# PuppyLight.net
KiCad netlist of a schematic drawn in Altium Designer
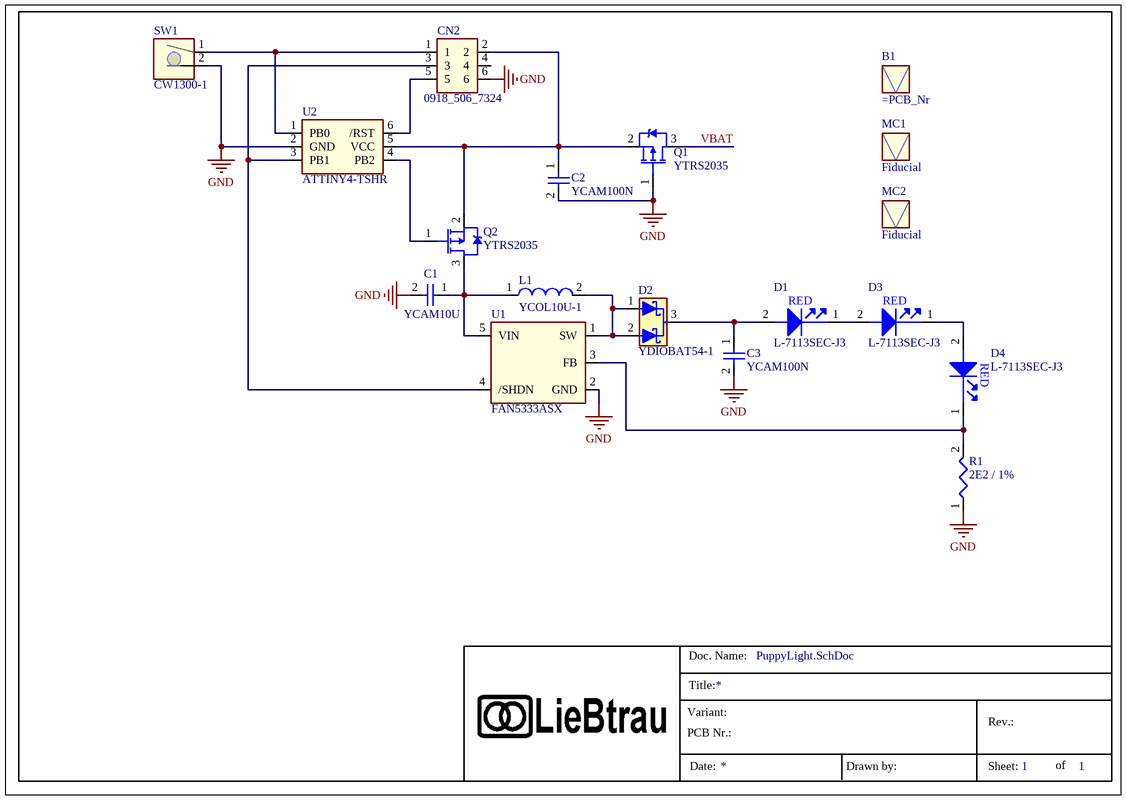
[diagram p0: PuppyLight.SchDoc]

(export (version "E")
  (design (tool "Eeschema 10.0.6"))
  (components
    (comp (ref "B1")
      (value "~")
      (footprint "MC_BoardNr")
      (fields (field (name "PART NUMBER") "BARE_PCB"))
      (libsource (lib "Testing") (part "BD_PCB"))
    )
    (comp (ref "C1") (value "YCAM10U") (footprint "CA_1206") (libsource (lib "Testing") (part "CA_NONPOL")))
    (comp (ref "C2") (value "YCAM100N") (footprint "CA_1206") (libsource (lib "Testing") (part "CA_NONPOL")))
    (comp (ref "C3") (value "YCAM100N") (footprint "CA_1206") (libsource (lib "Testing") (part "CA_NONPOL")))
    (comp (ref "CN2")
      (value "0918_506_7324")
      (footprint "CN_HARTING_918506X324")
      (fields (field (name "MANUFACTURER") "Harting"))
      (libsource (lib "Testing") (part "CN_2x3P"))
    )
    (comp (ref "D1")
      (value "L-7113SEC-J3")
      (footprint "DI_LED_5MM")
      (fields (field (name "MANUFACTURER") "Kingbright"))
      (libsource (lib "Testing") (part "DI_LED_RED_2"))
    )
    (comp (ref "D2")
      (value "YDIOBAT54-1")
      (footprint "SC_SOT23")
      (description "Dual Schottky Barrier Diode Common Cathode")
      (fields (field (name "MANUFACTURER") "Fairchild Semiconductor"))
      (libsource (lib "Testing") (part "DI_SCHOTTKY_2_CC"))
    )
    (comp (ref "D3")
      (value "L-7113SEC-J3")
      (footprint "DI_LED_5MM")
      (fields (field (name "MANUFACTURER") "Kingbright"))
      (libsource (lib "Testing") (part "DI_LED_RED_2"))
    )
    (comp (ref "D4")
      (value "L-7113SEC-J3")
      (footprint "DI_LED_5MM")
      (fields (field (name "MANUFACTURER") "Kingbright"))
      (libsource (lib "Testing") (part "DI_LED_RED_2"))
    )
    (comp (ref "L1")
      (value "YCOL10U-1")
      (footprint "CL_VISHAY_IHLP-2525CZ-01")
      (fields (field (name "MANUFACTURER") "Vishay Dale"))
      (libsource (lib "Testing") (part "CL_COIL"))
    )
    (comp (ref "MC1")
      (value "Fiducial")
      (footprint "MC_FIDUCIAL")
      (libsource (lib "Testing") (part "MC_MechPart_No_BOM"))
    )
    (comp (ref "MC2")
      (value "Fiducial")
      (footprint "MC_FIDUCIAL")
      (libsource (lib "Testing") (part "MC_MechPart_No_BOM"))
    )
    (comp (ref "Q1")
      (value "YTRS2035")
      (footprint "SC_SOT23")
      (fields (field (name "MANUFACTURER") "Diodes Inc."))
      (libsource (lib "Testing") (part "TR_PMOS"))
    )
    (comp (ref "Q2")
      (value "YTRS2035")
      (footprint "SC_SOT23")
      (fields (field (name "MANUFACTURER") "Diodes Inc."))
      (libsource (lib "Testing") (part "TR_PMOS"))
    )
    (comp (ref "R1")
      (value "2E2 / 1%")
      (footprint "RE_1206")
      (description "Resistor")
      (fields (field (name "PART NUMBER") "ASC1206-2R2FT5") (field (name "MANUFACTURER") "Welwyn"))
      (libsource (lib "Testing") (part "RE_RES"))
    )
    (comp (ref "SW1")
      (value "CW1300-1")
      (footprint "SW_TILT_Comus_CW1300-1")
      (fields (field (name "MANUFACTURER") "Comus"))
      (libsource (lib "Testing") (part "SW_TILT"))
    )
    (comp (ref "U1")
      (value "FAN5333ASX")
      (footprint "SC_SOT23-5AM")
      (fields (field (name "MANUFACTURER") "Fairchild Semi"))
      (libsource (lib "Testing") (part "IC_FAN5333"))
    )
    (comp (ref "U2")
      (value "ATTINY4-TSHR")
      (footprint "SC_SOT23-6")
      (fields (field (name "MANUFACTURER") "Atmel"))
      (libsource (lib "Testing") (part "IC_ATMEL_ATTINY9"))
    )
  )
  (nets
    (net (code "1") (name "/VBAT") (class "Default")
      (node (ref "Q1") (pin "3") (pinfunction "D_3") (pintype "passive"))
    )
    (net (code "2") (name "GND") (class "Default")
      (node (ref "C1") (pin "2") (pinfunction "2_2") (pintype "passive"))
      (node (ref "C2") (pin "2") (pinfunction "2_2") (pintype "passive"))
      (node (ref "C3") (pin "2") (pinfunction "2_2") (pintype "passive"))
      (node (ref "CN2") (pin "6") (pinfunction "6_6") (pintype "passive"))
      (node (ref "Q1") (pin "1") (pinfunction "G_1") (pintype "passive"))
      (node (ref "R1") (pin "1") (pinfunction "1_1") (pintype "passive"))
      (node (ref "SW1") (pin "2") (pinfunction "2_2") (pintype "passive"))
      (node (ref "U1") (pin "2") (pinfunction "GND_2") (pintype "passive"))
      (node (ref "U2") (pin "2") (pinfunction "GND_2") (pintype "passive"))
    )
    (net (code "3") (name "Net-(D1-A)") (class "Default")
      (node (ref "D1") (pin "1") (pinfunction "A_1") (pintype "passive"))
      (node (ref "D3") (pin "2") (pinfunction "C_2") (pintype "passive"))
    )
    (net (code "4") (name "Net-(D1-C)") (class "Default")
      (node (ref "C3") (pin "1") (pinfunction "1_1") (pintype "passive"))
      (node (ref "D1") (pin "2") (pinfunction "C_2") (pintype "passive"))
      (node (ref "D2") (pin "3") (pinfunction "C_3") (pintype "passive"))
    )
    (net (code "5") (name "Net-(D2-A1)") (class "Default")
      (node (ref "D2") (pin "1") (pinfunction "A1_1") (pintype "passive"))
      (node (ref "D2") (pin "2") (pinfunction "A2_2") (pintype "passive"))
      (node (ref "L1") (pin "2") (pinfunction "2_2") (pintype "passive"))
      (node (ref "U1") (pin "1") (pinfunction "SW_1") (pintype "passive"))
    )
    (net (code "6") (name "Net-(D3-A)") (class "Default")
      (node (ref "D3") (pin "1") (pinfunction "A_1") (pintype "passive"))
      (node (ref "D4") (pin "2") (pinfunction "C_2") (pintype "passive"))
    )
    (net (code "7") (name "Net-(D4-A)") (class "Default")
      (node (ref "D4") (pin "1") (pinfunction "A_1") (pintype "passive"))
      (node (ref "R1") (pin "2") (pinfunction "2_2") (pintype "passive"))
      (node (ref "U1") (pin "3") (pinfunction "FB_3") (pintype "passive"))
    )
    (net (code "8") (name "Net-(Q1-S)") (class "Default")
      (node (ref "C2") (pin "1") (pinfunction "1_1") (pintype "passive"))
      (node (ref "CN2") (pin "2") (pinfunction "2_2") (pintype "passive"))
      (node (ref "Q1") (pin "2") (pinfunction "S_2") (pintype "passive"))
      (node (ref "Q2") (pin "2") (pinfunction "S_2") (pintype "passive"))
      (node (ref "U2") (pin "5") (pinfunction "VCC_5") (pintype "passive"))
    )
    (net (code "9") (name "Net-(Q2-D)") (class "Default")
      (node (ref "C1") (pin "1") (pinfunction "1_1") (pintype "passive"))
      (node (ref "L1") (pin "1") (pinfunction "1_1") (pintype "passive"))
      (node (ref "Q2") (pin "3") (pinfunction "D_3") (pintype "passive"))
      (node (ref "U1") (pin "5") (pinfunction "VIN_5") (pintype "passive"))
    )
    (net (code "10") (name "Net-(Q2-G)") (class "Default")
      (node (ref "Q2") (pin "1") (pinfunction "G_1") (pintype "passive"))
      (node (ref "U2") (pin "4") (pinfunction "PB2_4") (pintype "passive"))
    )
    (net (code "11") (name "Net-(U1-{slash}SHDN)") (class "Default")
      (node (ref "CN2") (pin "3") (pinfunction "3_3") (pintype "passive"))
      (node (ref "U1") (pin "4") (pinfunction "/SHDN_4") (pintype "passive"))
      (node (ref "U2") (pin "3") (pinfunction "PB1_3") (pintype "passive"))
    )
    (net (code "12") (name "Net-(U2-PB0)") (class "Default")
      (node (ref "CN2") (pin "1") (pinfunction "1_1") (pintype "passive"))
      (node (ref "SW1") (pin "1") (pinfunction "1_1") (pintype "passive"))
      (node (ref "U2") (pin "1") (pinfunction "PB0_1") (pintype "passive"))
    )
    (net (code "13") (name "Net-(U2-{slash}RST)") (class "Default")
      (node (ref "CN2") (pin "5") (pinfunction "5_5") (pintype "passive"))
      (node (ref "U2") (pin "6") (pinfunction "/RST_6") (pintype "passive"))
    )
    (net (code "14") (name "unconnected-(CN2-Pad4)") (class "Default")
      (node (ref "CN2") (pin "4") (pinfunction "4_4") (pintype "passive"))
    )
  )
)
